# POWER.net
KiCad netlist of a schematic drawn in Altium Designer
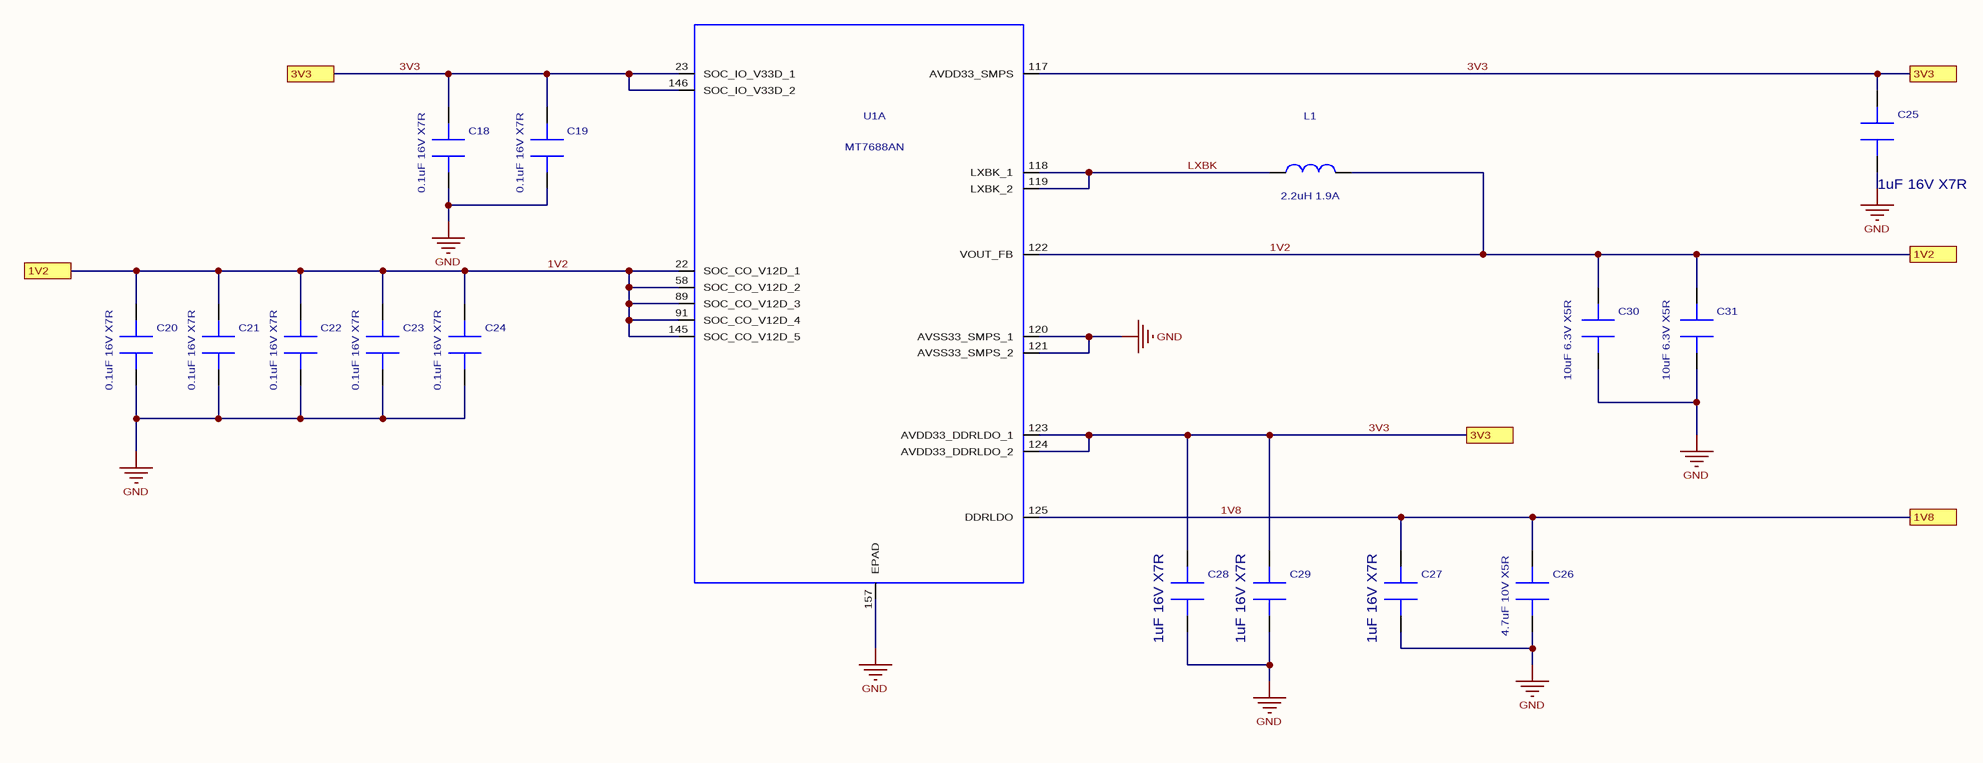
[diagram p0: POWER.SchDoc]

(export (version "E")
  (design (tool "Eeschema 10.0.6"))
  (components
    (comp (ref "C18")
      (value "0.1uF 16V X7R")
      (footprint "C0201")
      (description "CAP CER 0.1UF 16V X7R 0201")
      (fields
        (field (name "PART NUMBER") "GRM033Z71C104KE14D")
        (field (name "MANUFACTURER") "Murata Electronics")
      )
      (libsource (lib "NetworkModule") (part "CAP0201-104-16V-X7R"))
    )
    (comp (ref "C19")
      (value "0.1uF 16V X7R")
      (footprint "C0201")
      (description "CAP CER 0.1UF 16V X7R 0201")
      (fields
        (field (name "PART NUMBER") "GRM033Z71C104KE14D")
        (field (name "MANUFACTURER") "Murata Electronics")
      )
      (libsource (lib "NetworkModule") (part "CAP0201-104-16V-X7R"))
    )
    (comp (ref "C20")
      (value "0.1uF 16V X7R")
      (footprint "C0201")
      (description "CAP CER 0.1UF 16V X7R 0201")
      (fields
        (field (name "PART NUMBER") "GRM033Z71C104KE14D")
        (field (name "MANUFACTURER") "Murata Electronics")
      )
      (libsource (lib "NetworkModule") (part "CAP0201-104-16V-X7R"))
    )
    (comp (ref "C21")
      (value "0.1uF 16V X7R")
      (footprint "C0201")
      (description "CAP CER 0.1UF 16V X7R 0201")
      (fields
        (field (name "PART NUMBER") "GRM033Z71C104KE14D")
        (field (name "MANUFACTURER") "Murata Electronics")
      )
      (libsource (lib "NetworkModule") (part "CAP0201-104-16V-X7R"))
    )
    (comp (ref "C22")
      (value "0.1uF 16V X7R")
      (footprint "C0201")
      (description "CAP CER 0.1UF 16V X7R 0201")
      (fields
        (field (name "PART NUMBER") "GRM033Z71C104KE14D")
        (field (name "MANUFACTURER") "Murata Electronics")
      )
      (libsource (lib "NetworkModule") (part "CAP0201-104-16V-X7R"))
    )
    (comp (ref "C23")
      (value "0.1uF 16V X7R")
      (footprint "C0201")
      (description "CAP CER 0.1UF 16V X7R 0201")
      (fields
        (field (name "PART NUMBER") "GRM033Z71C104KE14D")
        (field (name "MANUFACTURER") "Murata Electronics")
      )
      (libsource (lib "NetworkModule") (part "CAP0201-104-16V-X7R"))
    )
    (comp (ref "C24")
      (value "0.1uF 16V X7R")
      (footprint "C0201")
      (description "CAP CER 0.1UF 16V X7R 0201")
      (fields
        (field (name "PART NUMBER") "GRM033Z71C104KE14D")
        (field (name "MANUFACTURER") "Murata Electronics")
      )
      (libsource (lib "NetworkModule") (part "CAP0201-104-16V-X7R"))
    )
    (comp (ref "C25")
      (value "1uF 16V X7R")
      (footprint "C0402")
      (description "CAP CER 1UF 6.3V X7R 0402")
      (fields
        (field (name "PART NUMBER") "GRM155R70J105KA12D")
        (field (name "MANUFACTURER") "Murata Electronics")
      )
      (libsource (lib "NetworkModule") (part "CAP0402-105-6.3V-X7R"))
    )
    (comp (ref "C26")
      (value "4.7uF 10V X5R")
      (footprint "C0402")
      (description "CAP CER 4.7UF 10V X5R 0402")
      (fields
        (field (name "PART NUMBER") "CL05A475MP5NRNC")
        (field (name "MANUFACTURER") "Samsung Electro-Mechanics")
      )
      (libsource (lib "NetworkModule") (part "CAP0402-475-10V-X5R"))
    )
    (comp (ref "C27")
      (value "1uF 16V X7R")
      (footprint "C0402")
      (description "CAP CER 1UF 6.3V X7R 0402")
      (fields
        (field (name "PART NUMBER") "GRM155R70J105KA12D")
        (field (name "MANUFACTURER") "Murata Electronics")
      )
      (libsource (lib "NetworkModule") (part "CAP0402-105-6.3V-X7R"))
    )
    (comp (ref "C28")
      (value "1uF 16V X7R")
      (footprint "C0402")
      (description "CAP CER 1UF 6.3V X7R 0402")
      (fields
        (field (name "PART NUMBER") "GRM155R70J105KA12D")
        (field (name "MANUFACTURER") "Murata Electronics")
      )
      (libsource (lib "NetworkModule") (part "CAP0402-105-6.3V-X7R"))
    )
    (comp (ref "C29")
      (value "1uF 16V X7R")
      (footprint "C0402")
      (description "CAP CER 1UF 6.3V X7R 0402")
      (fields
        (field (name "PART NUMBER") "GRM155R70J105KA12D")
        (field (name "MANUFACTURER") "Murata Electronics")
      )
      (libsource (lib "NetworkModule") (part "CAP0402-105-6.3V-X7R"))
    )
    (comp (ref "C30")
      (value "10uF 6.3V X5R")
      (footprint "C0402")
      (description "CAP CER 10UF 6.3V X5R 0402")
      (fields
        (field (name "PART NUMBER") "GRM155R60J106ME05J")
        (field (name "MANUFACTURER") "Murata Electronics")
      )
      (libsource (lib "NetworkModule") (part "CAP0402-475-10V-X5R"))
    )
    (comp (ref "C31")
      (value "10uF 6.3V X5R")
      (footprint "C0402")
      (description "CAP CER 10UF 6.3V X5R 0402")
      (fields
        (field (name "PART NUMBER") "GRM155R60J106ME05J")
        (field (name "MANUFACTURER") "Murata Electronics")
      )
      (libsource (lib "NetworkModule") (part "CAP0402-475-10V-X5R"))
    )
    (comp (ref "L1")
      (value "2.2uH 1.9A")
      (footprint "L0805")
      (description "POWER CHOKE MOLDED 2.2UH 1.9A")
      (fields
        (field (name "PART NUMBER") "WLPH201610M2R2PP")
        (field (name "MANUFACTURER") "Walsin Technology Corporation")
      )
      (libsource (lib "NetworkModule") (part "IND0805_2.2U_1.9A"))
    )
    (comp (ref "U1")
      (value "MT7688AN")
      (footprint "DR-QFN-128")
      (description "580Mhz 32bits Networking Processor")
      (fields (field (name "MANUFACTURER") "MediaTek Inc"))
      (libsource (lib "*") (part "MT7688AN"))
    )
  )
  (nets
    (net (code "1") (name "/1V2") (class "Default")
      (node (ref "C20") (pin "1") (pinfunction "1_1") (pintype "passive"))
      (node (ref "C21") (pin "1") (pinfunction "1_1") (pintype "passive"))
      (node (ref "C22") (pin "1") (pinfunction "1_1") (pintype "passive"))
      (node (ref "C23") (pin "1") (pinfunction "1_1") (pintype "passive"))
      (node (ref "C24") (pin "1") (pinfunction "1_1") (pintype "passive"))
      (node (ref "C30") (pin "1") (pinfunction "1_1") (pintype "passive"))
      (node (ref "C31") (pin "1") (pinfunction "1_1") (pintype "passive"))
      (node (ref "L1") (pin "2") (pinfunction "2_2") (pintype "passive"))
      (node (ref "U1") (pin "122") (pinfunction "VOUT_FB_122") (pintype "passive"))
      (node (ref "U1") (pin "145") (pinfunction "SOC_CO_V12D_5_145") (pintype "passive"))
      (node (ref "U1") (pin "22") (pinfunction "SOC_CO_V12D_1_22") (pintype "passive"))
      (node (ref "U1") (pin "58") (pinfunction "SOC_CO_V12D_2_58") (pintype "passive"))
      (node (ref "U1") (pin "89") (pinfunction "SOC_CO_V12D_3_89") (pintype "passive"))
      (node (ref "U1") (pin "91") (pinfunction "SOC_CO_V12D_4_91") (pintype "passive"))
    )
    (net (code "2") (name "/1V8") (class "Default")
      (node (ref "C26") (pin "1") (pinfunction "1_1") (pintype "passive"))
      (node (ref "C27") (pin "1") (pinfunction "1_1") (pintype "passive"))
      (node (ref "U1") (pin "125") (pinfunction "DDRLDO_125") (pintype "passive"))
    )
    (net (code "3") (name "/3V3") (class "Default")
      (node (ref "C18") (pin "1") (pinfunction "1_1") (pintype "passive"))
      (node (ref "C19") (pin "1") (pinfunction "1_1") (pintype "passive"))
      (node (ref "C25") (pin "1") (pinfunction "1_1") (pintype "passive"))
      (node (ref "C28") (pin "1") (pinfunction "1_1") (pintype "passive"))
      (node (ref "C29") (pin "1") (pinfunction "1_1") (pintype "passive"))
      (node (ref "U1") (pin "117") (pinfunction "AVDD33_SMPS_117") (pintype "passive"))
      (node (ref "U1") (pin "123") (pinfunction "AVDD33_DDRLDO_1_123") (pintype "passive"))
      (node (ref "U1") (pin "124") (pinfunction "AVDD33_DDRLDO_2_124") (pintype "passive"))
      (node (ref "U1") (pin "146") (pinfunction "SOC_IO_V33D_2_146") (pintype "passive"))
      (node (ref "U1") (pin "23") (pinfunction "SOC_IO_V33D_1_23") (pintype "passive"))
    )
    (net (code "4") (name "/LXBK") (class "Default")
      (node (ref "L1") (pin "1") (pinfunction "1_1") (pintype "passive"))
      (node (ref "U1") (pin "118") (pinfunction "LXBK_1_118") (pintype "passive"))
      (node (ref "U1") (pin "119") (pinfunction "LXBK_2_119") (pintype "passive"))
    )
    (net (code "5") (name "GND") (class "Default")
      (node (ref "C18") (pin "2") (pinfunction "2_2") (pintype "passive"))
      (node (ref "C19") (pin "2") (pinfunction "2_2") (pintype "passive"))
      (node (ref "C20") (pin "2") (pinfunction "2_2") (pintype "passive"))
      (node (ref "C21") (pin "2") (pinfunction "2_2") (pintype "passive"))
      (node (ref "C22") (pin "2") (pinfunction "2_2") (pintype "passive"))
      (node (ref "C23") (pin "2") (pinfunction "2_2") (pintype "passive"))
      (node (ref "C24") (pin "2") (pinfunction "2_2") (pintype "passive"))
      (node (ref "C25") (pin "2") (pinfunction "2_2") (pintype "passive"))
      (node (ref "C26") (pin "2") (pinfunction "2_2") (pintype "passive"))
      (node (ref "C27") (pin "2") (pinfunction "2_2") (pintype "passive"))
      (node (ref "C28") (pin "2") (pinfunction "2_2") (pintype "passive"))
      (node (ref "C29") (pin "2") (pinfunction "2_2") (pintype "passive"))
      (node (ref "C30") (pin "2") (pinfunction "2_2") (pintype "passive"))
      (node (ref "C31") (pin "2") (pinfunction "2_2") (pintype "passive"))
      (node (ref "U1") (pin "120") (pinfunction "AVSS33_SMPS_1_120") (pintype "passive"))
      (node (ref "U1") (pin "121") (pinfunction "AVSS33_SMPS_2_121") (pintype "passive"))
      (node (ref "U1") (pin "157") (pinfunction "EPAD_157") (pintype "passive"))
    )
  )
)
